# RainbowClock.net
KiCad netlist of a schematic drawn in Altium Designer
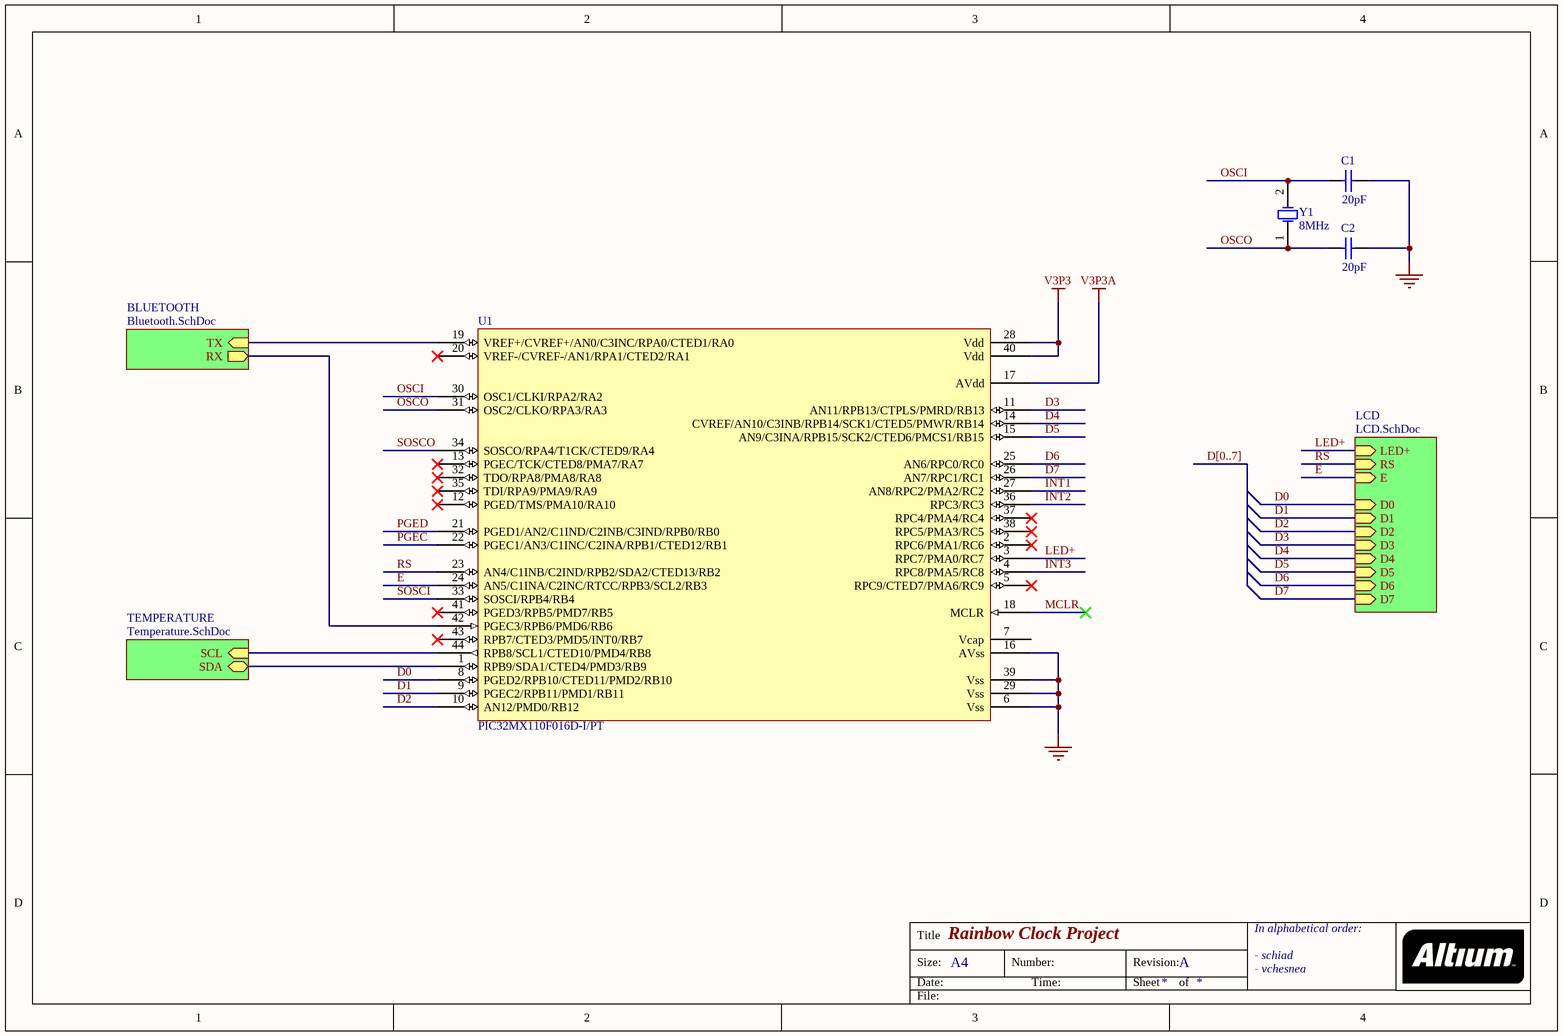
[diagram p0: RainbowClock.SchDoc]

(export (version "E")
  (design (tool "Eeschema 10.0.6"))
  (components
    (comp (ref "C1")
      (value "20pF")
      (footprint "RAD-0.3")
      (description "Capacitor")
      (fields (field (name "Comment") "Cap") (field (name "PUBLISHER") "Altium Limited"))
      (libsource (lib "Miscellaneous Devices") (part "Cap"))
    )
    (comp (ref "C2")
      (value "20pF")
      (footprint "RAD-0.3")
      (description "Capacitor")
      (fields (field (name "Comment") "Cap") (field (name "PUBLISHER") "Altium Limited"))
      (libsource (lib "Miscellaneous Devices") (part "Cap"))
    )
    (comp (ref "U1")
      (value "PIC32MX110F016D-I/PT")
      (description "44-Pin TQFP")
      (libsource (lib "Components") (part "PIC32MX110F016D-I/PT"))
    )
    (comp (ref "Y1")
      (value "8MHz")
      (footprint "R38")
      (description "Crystal Oscillator")
      (fields (field (name "PUBLISHER") "Altium Limited"))
      (libsource (lib "Miscellaneous Devices") (part "XTAL"))
    )
  )
  (nets
    (net (code "1") (name "/D0") (class "Default")
      (node (ref "U1") (pin "8") (pinfunction "PGED2/RPB10/CTED11/PMD2/RB10_8") (pintype "bidirectional"))
    )
    (net (code "2") (name "/D1") (class "Default")
      (node (ref "U1") (pin "9") (pinfunction "PGEC2/RPB11/PMD1/RB11_9") (pintype "bidirectional"))
    )
    (net (code "3") (name "/D2") (class "Default")
      (node (ref "U1") (pin "10") (pinfunction "AN12/PMD0/RB12_10") (pintype "bidirectional"))
    )
    (net (code "4") (name "/D3") (class "Default")
      (node (ref "U1") (pin "11") (pinfunction "AN11/RPB13/CTPLS/PMRD/RB13_11") (pintype "bidirectional"))
    )
    (net (code "5") (name "/D4") (class "Default")
      (node (ref "U1") (pin "14") (pinfunction "CVREF/AN10/C3INB/RPB14/SCK1/CTED5/PMWR/RB14_14") (pintype "bidirectional"))
    )
    (net (code "6") (name "/D5") (class "Default")
      (node (ref "U1") (pin "15") (pinfunction "AN9/C3INA/RPB15/SCK2/CTED6/PMCS1/RB15_15") (pintype "bidirectional"))
    )
    (net (code "7") (name "/D6") (class "Default")
      (node (ref "U1") (pin "25") (pinfunction "AN6/RPC0/RC0_25") (pintype "bidirectional"))
    )
    (net (code "8") (name "/D7") (class "Default")
      (node (ref "U1") (pin "26") (pinfunction "AN7/RPC1/RC1_26") (pintype "bidirectional"))
    )
    (net (code "10") (name "/E") (class "Default")
      (node (ref "U1") (pin "24") (pinfunction "AN5/C1INA/C2INC/RTCC/RPB3/SCL2/RB3_24") (pintype "bidirectional"))
    )
    (net (code "11") (name "/INT1") (class "Default")
      (node (ref "U1") (pin "27") (pinfunction "AN8/RPC2/PMA2/RC2_27") (pintype "bidirectional"))
    )
    (net (code "12") (name "/INT2") (class "Default")
      (node (ref "U1") (pin "36") (pinfunction "RPC3/RC3_36") (pintype "bidirectional"))
    )
    (net (code "13") (name "/INT3") (class "Default")
      (node (ref "U1") (pin "4") (pinfunction "RPC8/PMA5/RC8_4") (pintype "bidirectional"))
    )
    (net (code "14") (name "/LED+") (class "Default")
      (node (ref "U1") (pin "3") (pinfunction "RPC7/PMA0/RC7_3") (pintype "bidirectional"))
    )
    (net (code "15") (name "/MCLR") (class "Default")
      (node (ref "U1") (pin "18") (pinfunction "MCLR_18") (pintype "input+no_connect"))
    )
    (net (code "16") (name "/OSCI") (class "Default")
      (node (ref "C1") (pin "1") (pinfunction "1_1") (pintype "passive"))
      (node (ref "U1") (pin "30") (pinfunction "OSC1/CLKI/RPA2/RA2_30") (pintype "bidirectional"))
      (node (ref "Y1") (pin "2") (pinfunction "OSC2_2") (pintype "passive"))
    )
    (net (code "17") (name "/OSCO") (class "Default")
      (node (ref "C2") (pin "1") (pinfunction "1_1") (pintype "passive"))
      (node (ref "U1") (pin "31") (pinfunction "OSC2/CLKO/RPA3/RA3_31") (pintype "bidirectional"))
      (node (ref "Y1") (pin "1") (pinfunction "OSC1_1") (pintype "passive"))
    )
    (net (code "18") (name "/PGEC") (class "Default")
      (node (ref "U1") (pin "22") (pinfunction "PGEC1/AN3/C1INC/C2INA/RPB1/CTED12/RB1_22") (pintype "bidirectional"))
    )
    (net (code "19") (name "/PGED") (class "Default")
      (node (ref "U1") (pin "21") (pinfunction "PGED1/AN2/C1IND/C2INB/C3IND/RPB0/RB0_21") (pintype "bidirectional"))
    )
    (net (code "20") (name "/RS") (class "Default")
      (node (ref "U1") (pin "23") (pinfunction "AN4/C1INB/C2IND/RPB2/SDA2/CTED13/RB2_23") (pintype "bidirectional"))
    )
    (net (code "21") (name "/RX") (class "Default")
      (node (ref "U1") (pin "42") (pinfunction "PGEC3/RPB6/PMD6/RB6_42") (pintype "input"))
    )
    (net (code "22") (name "/SCL") (class "Default")
      (node (ref "U1") (pin "44") (pinfunction "RPB8/SCL1/CTED10/PMD4/RB8_44") (pintype "output"))
    )
    (net (code "23") (name "/SDA") (class "Default")
      (node (ref "U1") (pin "1") (pinfunction "RPB9/SDA1/CTED4/PMD3/RB9_1") (pintype "bidirectional"))
    )
    (net (code "24") (name "/SOSCI") (class "Default")
      (node (ref "U1") (pin "33") (pinfunction "SOSCI/RPB4/RB4_33") (pintype "bidirectional"))
    )
    (net (code "25") (name "/SOSCO") (class "Default")
      (node (ref "U1") (pin "34") (pinfunction "SOSCO/RPA4/T1CK/CTED9/RA4_34") (pintype "bidirectional"))
    )
    (net (code "26") (name "/TX") (class "Default")
      (node (ref "U1") (pin "19") (pinfunction "VREF+/CVREF+/AN0/C3INC/RPA0/CTED1/RA0_19") (pintype "bidirectional"))
    )
    (net (code "27") (name "GND") (class "Default")
      (node (ref "C1") (pin "2") (pinfunction "2_2") (pintype "passive"))
      (node (ref "C2") (pin "2") (pinfunction "2_2") (pintype "passive"))
      (node (ref "U1") (pin "16") (pinfunction "AVss_16") (pintype "power_in"))
      (node (ref "U1") (pin "29") (pinfunction "Vss_29") (pintype "power_in"))
      (node (ref "U1") (pin "39") (pinfunction "Vss_39") (pintype "power_in"))
      (node (ref "U1") (pin "6") (pinfunction "Vss_6") (pintype "power_in"))
    )
    (net (code "28") (name "V3P3") (class "Default")
      (node (ref "U1") (pin "28") (pinfunction "Vdd_28") (pintype "power_in"))
      (node (ref "U1") (pin "40") (pinfunction "Vdd_40") (pintype "power_in"))
    )
    (net (code "29") (name "V3P3A") (class "Default")
      (node (ref "U1") (pin "17") (pinfunction "AVdd_17") (pintype "power_in"))
    )
    (net (code "30") (name "unconnected-(U1-PGEC{slash}TCK{slash}CTED8{slash}PMA7{slash}RA7-Pad13)") (class "Default")
      (node (ref "U1") (pin "13") (pinfunction "PGEC/TCK/CTED8/PMA7/RA7_13") (pintype "bidirectional+no_connect"))
    )
    (net (code "31") (name "unconnected-(U1-PGED3{slash}RPB5{slash}PMD7{slash}RB5-Pad41)") (class "Default")
      (node (ref "U1") (pin "41") (pinfunction "PGED3/RPB5/PMD7/RB5_41") (pintype "bidirectional+no_connect"))
    )
    (net (code "32") (name "unconnected-(U1-PGED{slash}TMS{slash}PMA10{slash}RA10-Pad12)") (class "Default")
      (node (ref "U1") (pin "12") (pinfunction "PGED/TMS/PMA10/RA10_12") (pintype "bidirectional+no_connect"))
    )
    (net (code "33") (name "unconnected-(U1-RPB7{slash}CTED3{slash}PMD5{slash}INT0{slash}RB7-Pad43)") (class "Default")
      (node (ref "U1") (pin "43") (pinfunction "RPB7/CTED3/PMD5/INT0/RB7_43") (pintype "bidirectional+no_connect"))
    )
    (net (code "34") (name "unconnected-(U1-RPC4{slash}PMA4{slash}RC4-Pad37)") (class "Default")
      (node (ref "U1") (pin "37") (pinfunction "RPC4/PMA4/RC4_37") (pintype "bidirectional+no_connect"))
    )
    (net (code "35") (name "unconnected-(U1-RPC5{slash}PMA3{slash}RC5-Pad38)") (class "Default")
      (node (ref "U1") (pin "38") (pinfunction "RPC5/PMA3/RC5_38") (pintype "bidirectional+no_connect"))
    )
    (net (code "36") (name "unconnected-(U1-RPC6{slash}PMA1{slash}RC6-Pad2)") (class "Default")
      (node (ref "U1") (pin "2") (pinfunction "RPC6/PMA1/RC6_2") (pintype "bidirectional+no_connect"))
    )
    (net (code "37") (name "unconnected-(U1-RPC9{slash}CTED7{slash}PMA6{slash}RC9-Pad5)") (class "Default")
      (node (ref "U1") (pin "5") (pinfunction "RPC9/CTED7/PMA6/RC9_5") (pintype "bidirectional+no_connect"))
    )
    (net (code "38") (name "unconnected-(U1-TDI{slash}RPA9{slash}PMA9{slash}RA9-Pad35)") (class "Default")
      (node (ref "U1") (pin "35") (pinfunction "TDI/RPA9/PMA9/RA9_35") (pintype "bidirectional+no_connect"))
    )
    (net (code "39") (name "unconnected-(U1-TDO{slash}RPA8{slash}PMA8{slash}RA8-Pad32)") (class "Default")
      (node (ref "U1") (pin "32") (pinfunction "TDO/RPA8/PMA8/RA8_32") (pintype "bidirectional+no_connect"))
    )
    (net (code "40") (name "unconnected-(U1-VREF-{slash}CVREF-{slash}AN1{slash}RPA1{slash}CTED2{slash}RA1-Pad20)") (class "Default")
      (node (ref "U1") (pin "20") (pinfunction "VREF-/CVREF-/AN1/RPA1/CTED2/RA1_20") (pintype "bidirectional+no_connect"))
    )
    (net (code "41") (name "unconnected-(U1-Vcap-Pad7)") (class "Default")
      (node (ref "U1") (pin "7") (pinfunction "Vcap_7") (pintype "power_in"))
    )
  )
)
